# sensore-linea.net
KiCad netlist of a schematic drawn in EAGLE
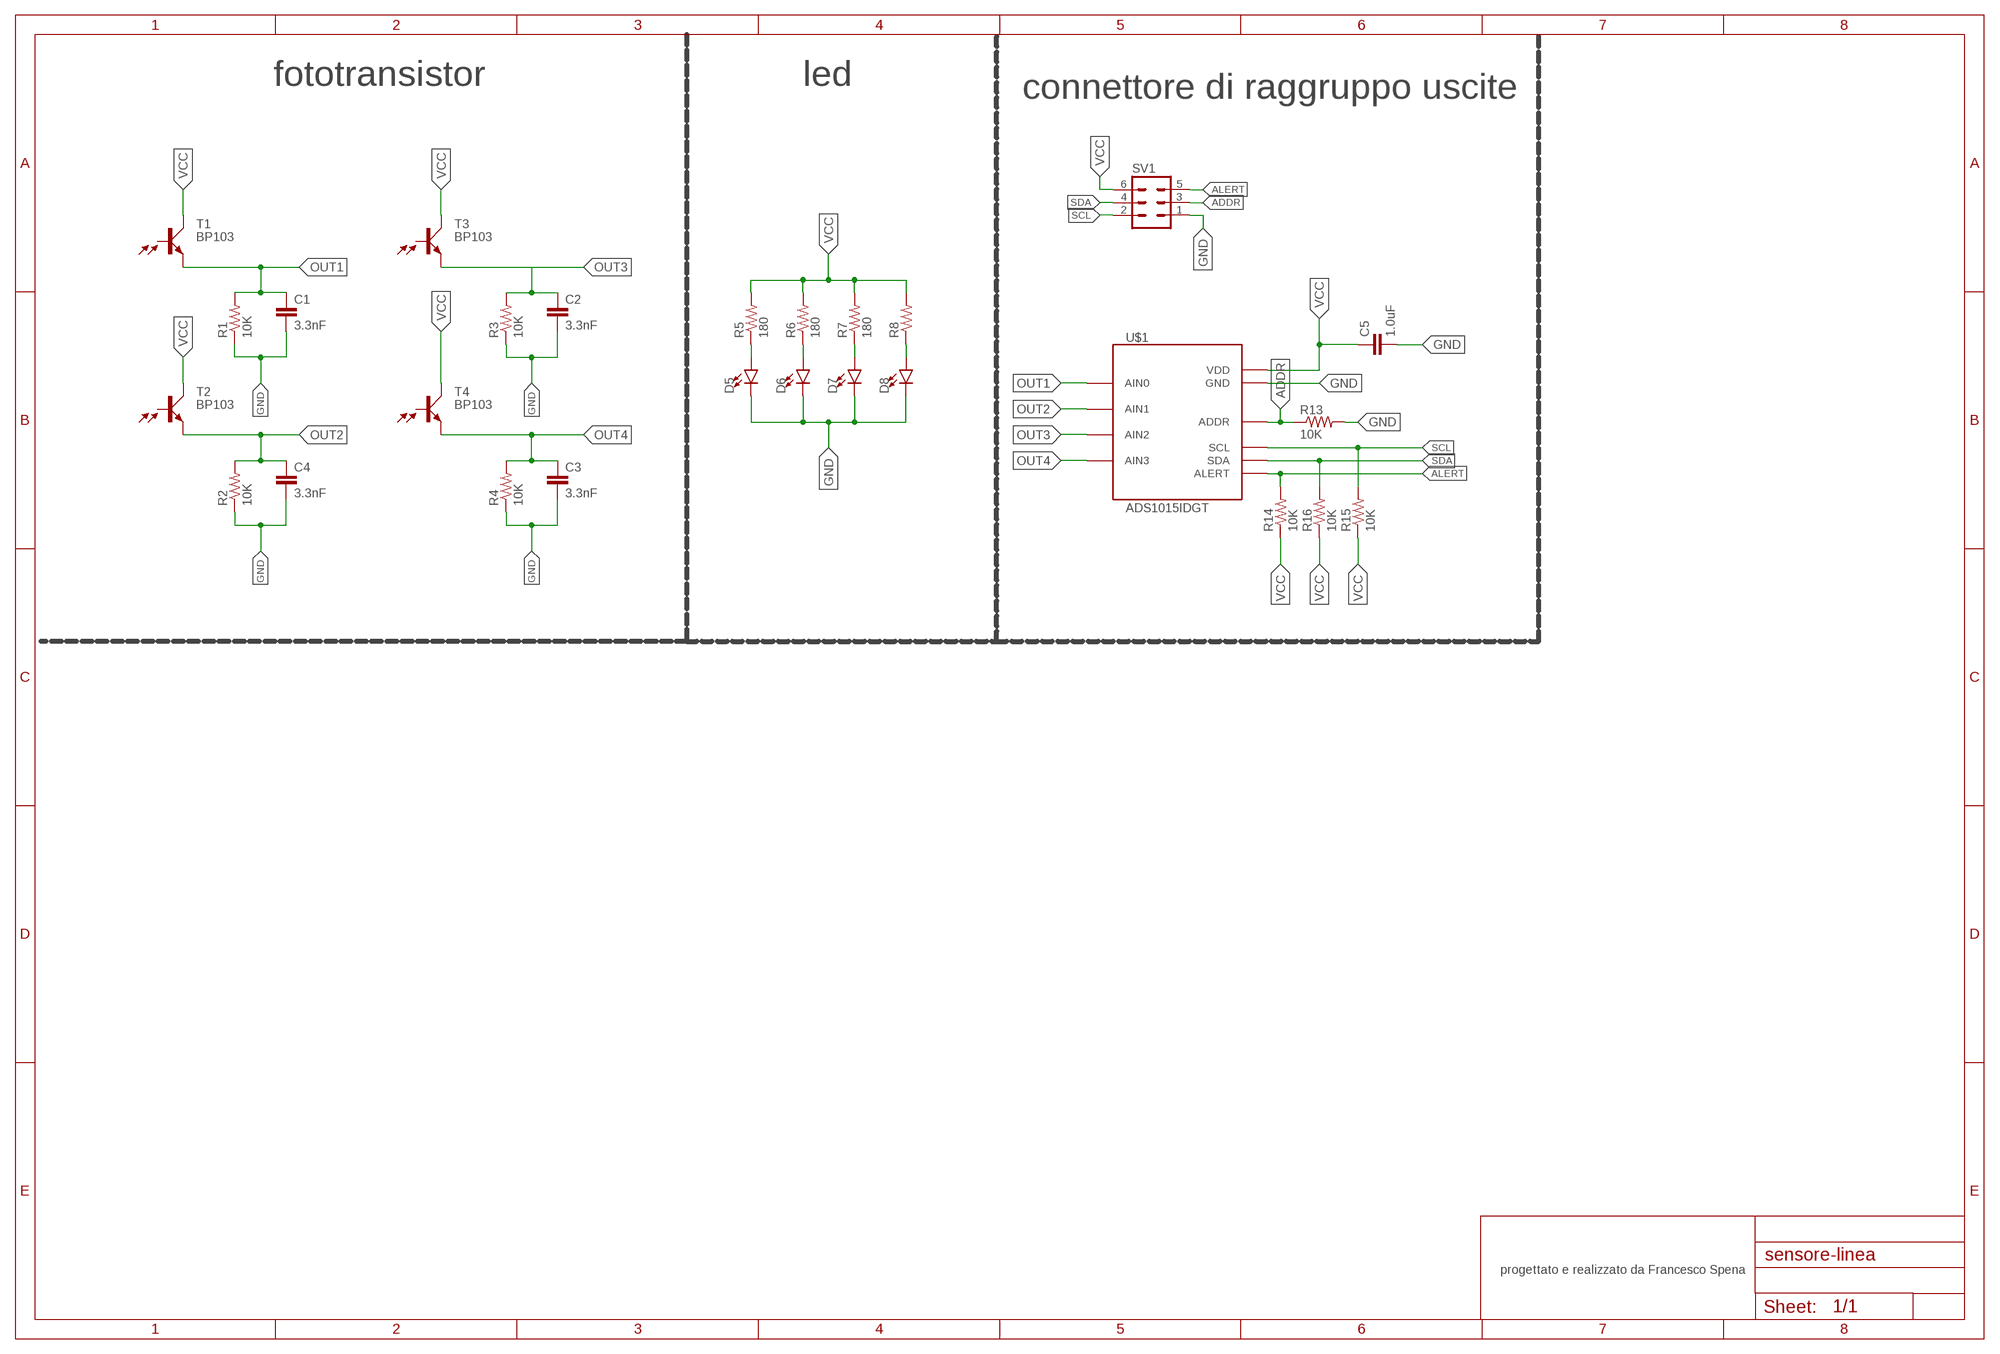
[diagram p0: schematic, sheet 1]

(export (version "E")
  (design (tool "Eeschema 10.0.6"))
  (components
    (comp (ref "C1")
      (value "3.3nF")
      (footprint "eagle-import:0603")
      (libsource (lib "eagle-import") (part "3.3NF-0603-100V-10%"))
    )
    (comp (ref "C2")
      (value "3.3nF")
      (footprint "eagle-import:0603")
      (libsource (lib "eagle-import") (part "3.3NF-0603-100V-10%"))
    )
    (comp (ref "C3")
      (value "3.3nF")
      (footprint "eagle-import:0603")
      (libsource (lib "eagle-import") (part "3.3NF-0603-100V-10%"))
    )
    (comp (ref "C4")
      (value "3.3nF")
      (footprint "eagle-import:0603")
      (libsource (lib "eagle-import") (part "3.3NF-0603-100V-10%"))
    )
    (comp (ref "C5")
      (value "1.0uF")
      (footprint "eagle-import:0402")
      (libsource (lib "eagle-import") (part "1.0UF-0402-16V-10%"))
    )
    (comp (ref "D5")
      (value "LED3MM")
      (footprint "eagle-import:LED_3MM")
      (libsource (lib "eagle-import") (part "LED3MM"))
    )
    (comp (ref "D6")
      (value "LED3MM")
      (footprint "eagle-import:LED_3MM")
      (libsource (lib "eagle-import") (part "LED3MM"))
    )
    (comp (ref "D7")
      (value "LED3MM")
      (footprint "eagle-import:LED_3MM")
      (libsource (lib "eagle-import") (part "LED3MM"))
    )
    (comp (ref "D8")
      (value "LED3MM")
      (footprint "eagle-import:LED_3MM")
      (libsource (lib "eagle-import") (part "LED3MM"))
    )
    (comp (ref "R1")
      (value "10K")
      (footprint "eagle-import:0204_7")
      (libsource (lib "eagle-import") (part "resistor_348_R-US_0204/7"))
    )
    (comp (ref "R2")
      (value "10K")
      (footprint "eagle-import:0204_7")
      (libsource (lib "eagle-import") (part "resistor_348_R-US_0204/7"))
    )
    (comp (ref "R3")
      (value "10K")
      (footprint "eagle-import:0204_7")
      (libsource (lib "eagle-import") (part "resistor_348_R-US_0204/7"))
    )
    (comp (ref "R4")
      (value "10K")
      (footprint "eagle-import:0204_7")
      (libsource (lib "eagle-import") (part "resistor_348_R-US_0204/7"))
    )
    (comp (ref "R5")
      (value "180")
      (footprint "eagle-import:0204_7")
      (libsource (lib "eagle-import") (part "R-US_0204/7"))
    )
    (comp (ref "R6")
      (value "180")
      (footprint "eagle-import:0204_7")
      (libsource (lib "eagle-import") (part "R-US_0204/7"))
    )
    (comp (ref "R7")
      (value "180")
      (footprint "eagle-import:0204_7")
      (libsource (lib "eagle-import") (part "R-US_0204/7"))
    )
    (comp (ref "R8")
      (value "R-US_0204/7")
      (footprint "eagle-import:0204_7")
      (libsource (lib "eagle-import") (part "R-US_0204/7"))
    )
    (comp (ref "R13")
      (value "10K")
      (footprint "eagle-import:0204_7")
      (libsource (lib "eagle-import") (part "resistor_348_R-US_0204/7"))
    )
    (comp (ref "R14")
      (value "10K")
      (footprint "eagle-import:0204_7")
      (libsource (lib "eagle-import") (part "resistor_348_R-US_0204/7"))
    )
    (comp (ref "R15")
      (value "10K")
      (footprint "eagle-import:0204_7")
      (libsource (lib "eagle-import") (part "resistor_348_R-US_0204/7"))
    )
    (comp (ref "R16")
      (value "10K")
      (footprint "eagle-import:0204_7")
      (libsource (lib "eagle-import") (part "resistor_348_R-US_0204/7"))
    )
    (comp (ref "SV1")
      (value "MA03-2")
      (footprint "eagle-import:MA03-2")
      (libsource (lib "eagle-import") (part "MA03-2"))
    )
    (comp (ref "T1")
      (value "BP103")
      (footprint "eagle-import:BP103")
      (libsource (lib "eagle-import") (part "BP103"))
    )
    (comp (ref "T2")
      (value "BP103")
      (footprint "eagle-import:BP103")
      (libsource (lib "eagle-import") (part "BP103"))
    )
    (comp (ref "T3")
      (value "BP103")
      (footprint "eagle-import:BP103")
      (libsource (lib "eagle-import") (part "BP103"))
    )
    (comp (ref "T4")
      (value "BP103")
      (footprint "eagle-import:BP103")
      (libsource (lib "eagle-import") (part "BP103"))
    )
    (comp (ref "U$1")
      (value "ADS1015IDGT")
      (footprint "eagle-import:MSOP10_0.5")
      (libsource (lib "eagle-import") (part "ADS1015IDGT"))
    )
  )
  (nets
    (net (code "1") (name "ADDR") (class "Default")
      (node (ref "R13") (pin "1") (pinfunction "1_1") (pintype "passive"))
      (node (ref "SV1") (pin "3") (pinfunction "3_3") (pintype "passive"))
      (node (ref "U$1") (pin "1") (pinfunction "ADDR_1") (pintype "input"))
    )
    (net (code "2") (name "ALERT") (class "Default")
      (node (ref "R14") (pin "2") (pinfunction "2_2") (pintype "passive"))
      (node (ref "SV1") (pin "5") (pinfunction "5_5") (pintype "passive"))
      (node (ref "U$1") (pin "2") (pinfunction "ALERT_2") (pintype "output"))
    )
    (net (code "3") (name "GND") (class "Default")
      (node (ref "C1") (pin "2") (pinfunction "2_2") (pintype "passive"))
      (node (ref "C2") (pin "2") (pinfunction "2_2") (pintype "passive"))
      (node (ref "C3") (pin "2") (pinfunction "2_2") (pintype "passive"))
      (node (ref "C4") (pin "2") (pinfunction "2_2") (pintype "passive"))
      (node (ref "C5") (pin "2") (pinfunction "2_2") (pintype "passive"))
      (node (ref "D5") (pin "K") (pinfunction "C_K") (pintype "passive"))
      (node (ref "D6") (pin "K") (pinfunction "C_K") (pintype "passive"))
      (node (ref "D7") (pin "K") (pinfunction "C_K") (pintype "passive"))
      (node (ref "D8") (pin "K") (pinfunction "C_K") (pintype "passive"))
      (node (ref "R1") (pin "1") (pinfunction "1_1") (pintype "passive"))
      (node (ref "R13") (pin "2") (pinfunction "2_2") (pintype "passive"))
      (node (ref "R2") (pin "1") (pinfunction "1_1") (pintype "passive"))
      (node (ref "R3") (pin "1") (pinfunction "1_1") (pintype "passive"))
      (node (ref "R4") (pin "1") (pinfunction "1_1") (pintype "passive"))
      (node (ref "SV1") (pin "1") (pinfunction "1_1") (pintype "passive"))
      (node (ref "U$1") (pin "3") (pinfunction "GND_3") (pintype "power_in"))
    )
    (net (code "4") (name "Net-(D5-PadA)") (class "Default")
      (node (ref "D5") (pin "A") (pinfunction "A_A") (pintype "passive"))
      (node (ref "R5") (pin "1") (pinfunction "1_1") (pintype "passive"))
    )
    (net (code "5") (name "Net-(D6-PadA)") (class "Default")
      (node (ref "D6") (pin "A") (pinfunction "A_A") (pintype "passive"))
      (node (ref "R6") (pin "1") (pinfunction "1_1") (pintype "passive"))
    )
    (net (code "6") (name "Net-(D7-PadA)") (class "Default")
      (node (ref "D7") (pin "A") (pinfunction "A_A") (pintype "passive"))
      (node (ref "R7") (pin "1") (pinfunction "1_1") (pintype "passive"))
    )
    (net (code "7") (name "Net-(D8-PadA)") (class "Default")
      (node (ref "D8") (pin "A") (pinfunction "A_A") (pintype "passive"))
      (node (ref "R8") (pin "1") (pinfunction "1_1") (pintype "passive"))
    )
    (net (code "8") (name "OUT1") (class "Default")
      (node (ref "C1") (pin "1") (pinfunction "1_1") (pintype "passive"))
      (node (ref "R1") (pin "2") (pinfunction "2_2") (pintype "passive"))
      (node (ref "T1") (pin "E") (pinfunction "E_E") (pintype "passive"))
      (node (ref "U$1") (pin "4") (pinfunction "AIN0_4") (pintype "input"))
    )
    (net (code "9") (name "OUT2") (class "Default")
      (node (ref "C4") (pin "1") (pinfunction "1_1") (pintype "passive"))
      (node (ref "R2") (pin "2") (pinfunction "2_2") (pintype "passive"))
      (node (ref "T2") (pin "E") (pinfunction "E_E") (pintype "passive"))
      (node (ref "U$1") (pin "5") (pinfunction "AIN1_5") (pintype "input"))
    )
    (net (code "10") (name "OUT3") (class "Default")
      (node (ref "C2") (pin "1") (pinfunction "1_1") (pintype "passive"))
      (node (ref "R3") (pin "2") (pinfunction "2_2") (pintype "passive"))
      (node (ref "T3") (pin "E") (pinfunction "E_E") (pintype "passive"))
      (node (ref "U$1") (pin "6") (pinfunction "AIN2_6") (pintype "input"))
    )
    (net (code "11") (name "OUT4") (class "Default")
      (node (ref "C3") (pin "1") (pinfunction "1_1") (pintype "passive"))
      (node (ref "R4") (pin "2") (pinfunction "2_2") (pintype "passive"))
      (node (ref "T4") (pin "E") (pinfunction "E_E") (pintype "passive"))
      (node (ref "U$1") (pin "7") (pinfunction "AIN3_7") (pintype "input"))
    )
    (net (code "12") (name "SCL") (class "Default")
      (node (ref "R15") (pin "2") (pinfunction "2_2") (pintype "passive"))
      (node (ref "SV1") (pin "2") (pinfunction "2_2") (pintype "passive"))
      (node (ref "U$1") (pin "10") (pinfunction "SCL_10") (pintype "bidirectional"))
    )
    (net (code "13") (name "SDA") (class "Default")
      (node (ref "R16") (pin "2") (pinfunction "2_2") (pintype "passive"))
      (node (ref "SV1") (pin "4") (pinfunction "4_4") (pintype "passive"))
      (node (ref "U$1") (pin "9") (pinfunction "SDA_9") (pintype "bidirectional"))
    )
    (net (code "14") (name "VCC") (class "Default")
      (node (ref "C5") (pin "1") (pinfunction "1_1") (pintype "passive"))
      (node (ref "R14") (pin "1") (pinfunction "1_1") (pintype "passive"))
      (node (ref "R15") (pin "1") (pinfunction "1_1") (pintype "passive"))
      (node (ref "R16") (pin "1") (pinfunction "1_1") (pintype "passive"))
      (node (ref "R5") (pin "2") (pinfunction "2_2") (pintype "passive"))
      (node (ref "R6") (pin "2") (pinfunction "2_2") (pintype "passive"))
      (node (ref "R7") (pin "2") (pinfunction "2_2") (pintype "passive"))
      (node (ref "R8") (pin "2") (pinfunction "2_2") (pintype "passive"))
      (node (ref "SV1") (pin "6") (pinfunction "6_6") (pintype "passive"))
      (node (ref "T1") (pin "C") (pinfunction "C_C") (pintype "passive"))
      (node (ref "T2") (pin "C") (pinfunction "C_C") (pintype "passive"))
      (node (ref "T3") (pin "C") (pinfunction "C_C") (pintype "passive"))
      (node (ref "T4") (pin "C") (pinfunction "C_C") (pintype "passive"))
      (node (ref "U$1") (pin "8") (pinfunction "VDD_8") (pintype "power_in"))
    )
    (net (code "15") (name "unconnected-(T1-PadB)") (class "Default")
      (node (ref "T1") (pin "B") (pinfunction "B_B") (pintype "passive"))
    )
    (net (code "16") (name "unconnected-(T2-PadB)") (class "Default")
      (node (ref "T2") (pin "B") (pinfunction "B_B") (pintype "passive"))
    )
    (net (code "17") (name "unconnected-(T3-PadB)") (class "Default")
      (node (ref "T3") (pin "B") (pinfunction "B_B") (pintype "passive"))
    )
    (net (code "18") (name "unconnected-(T4-PadB)") (class "Default")
      (node (ref "T4") (pin "B") (pinfunction "B_B") (pintype "passive"))
    )
  )
)
